# sensor.net
KiCad netlist of a schematic drawn in Altium Designer
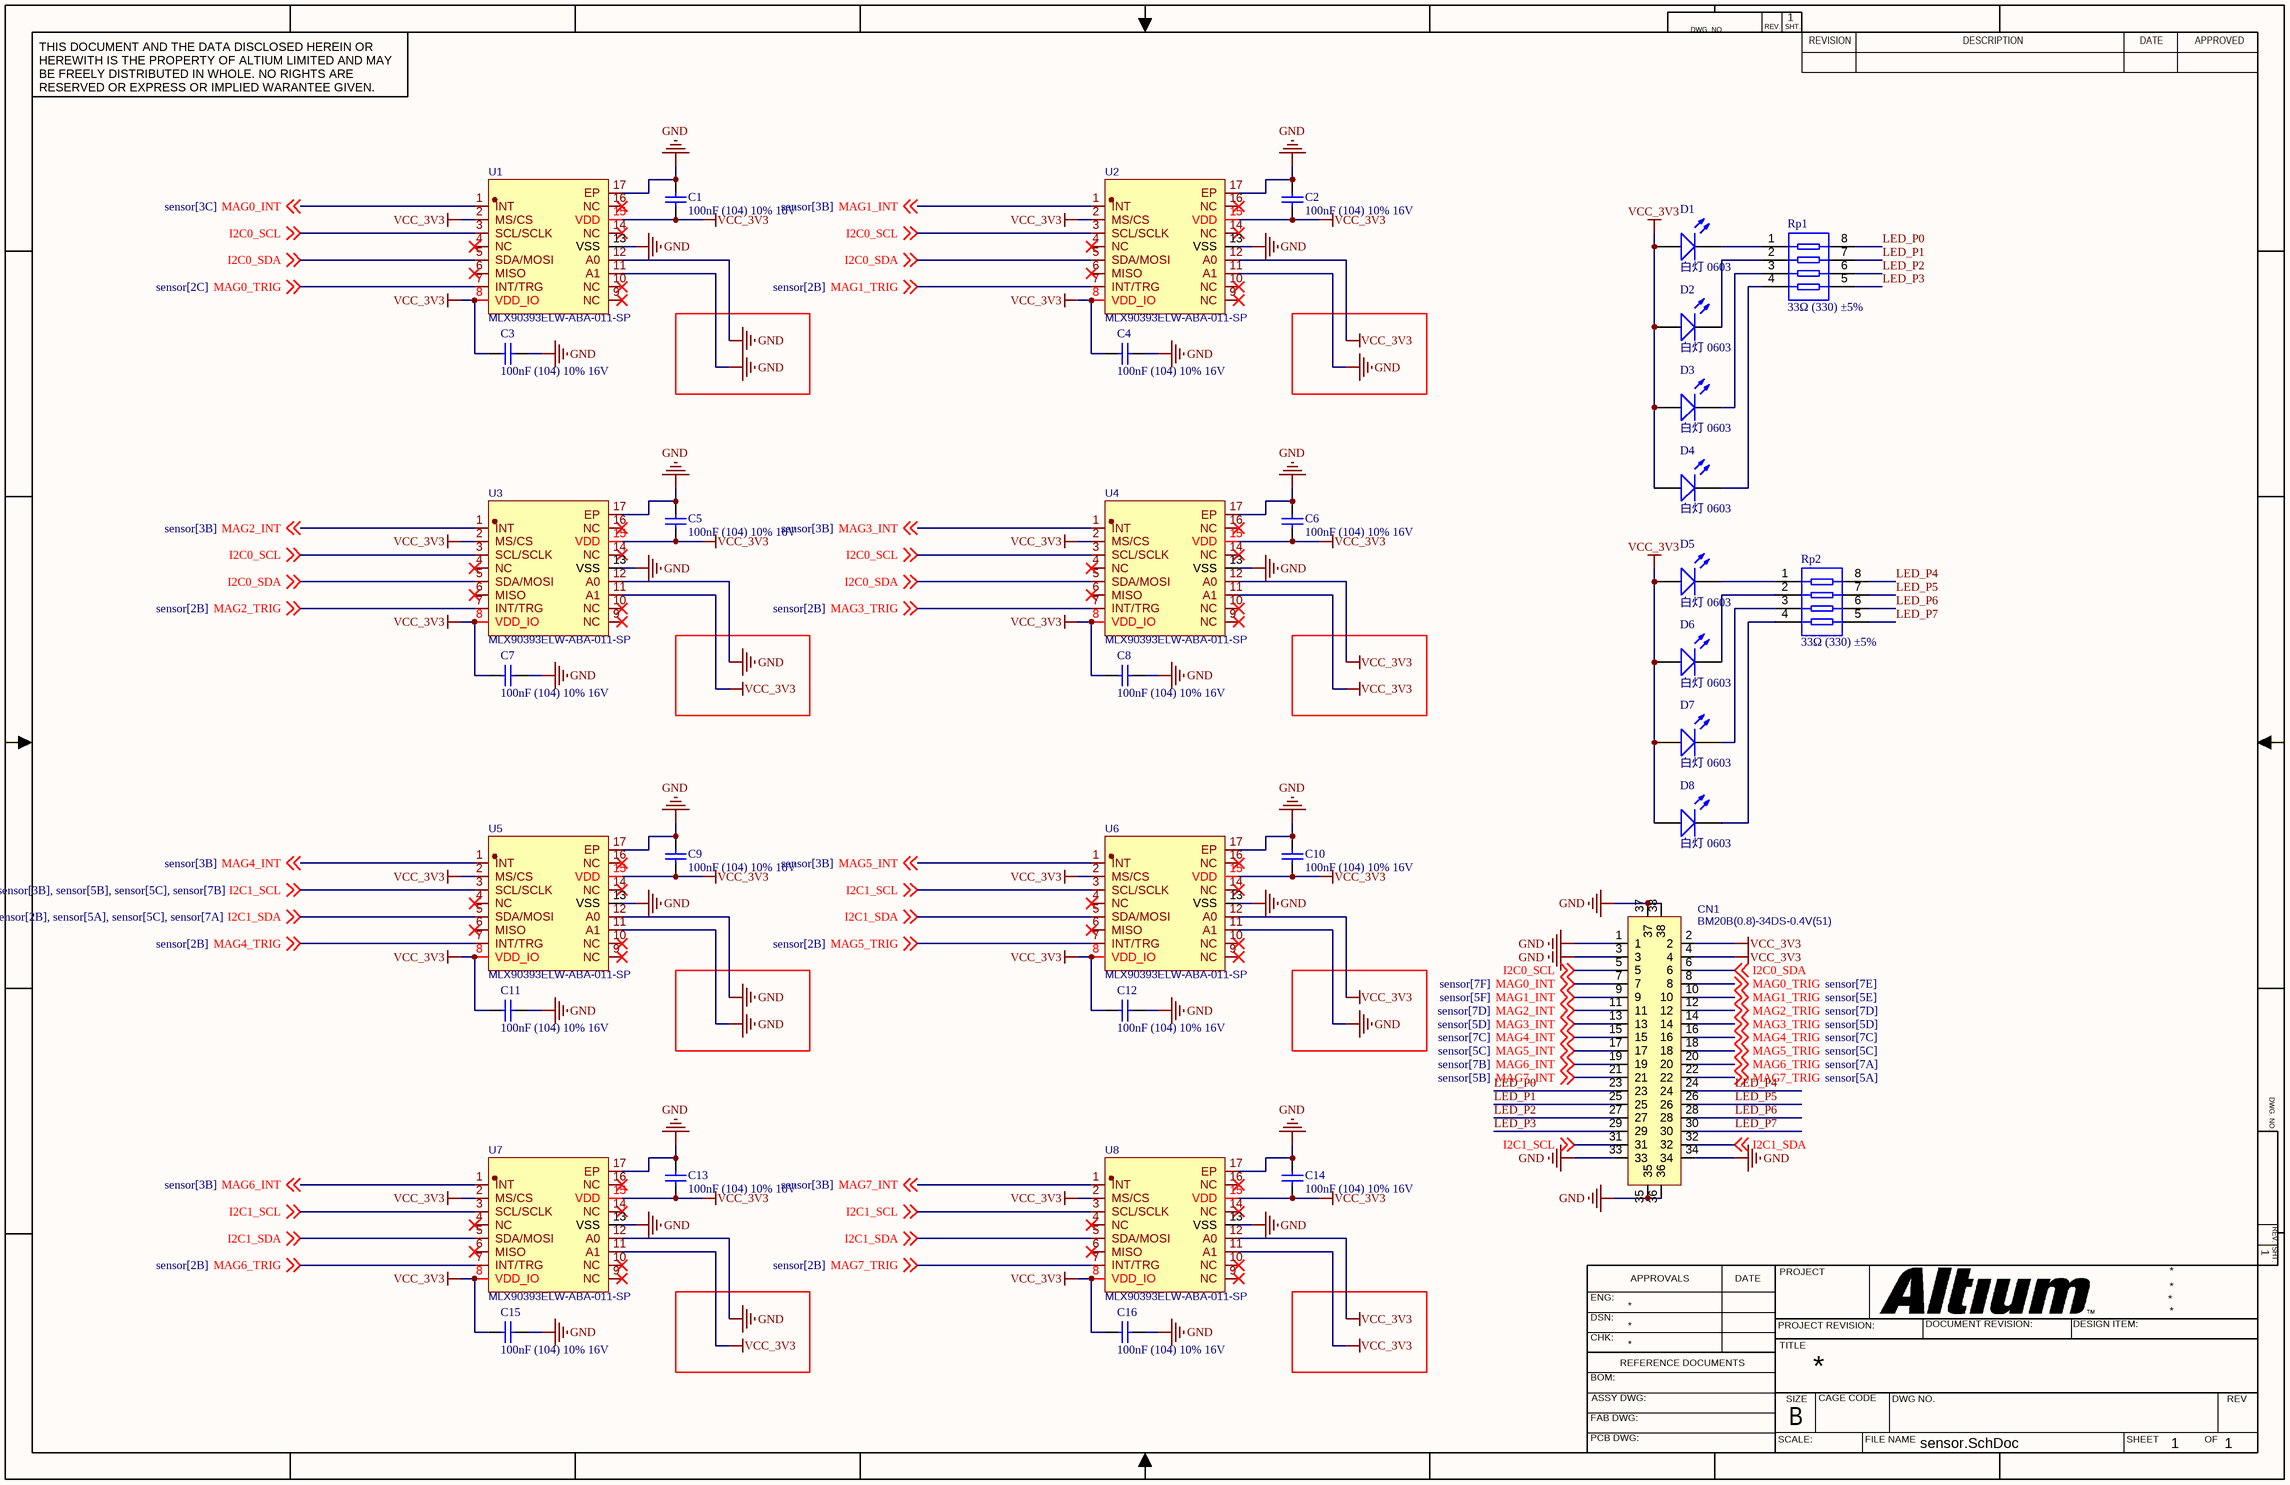
[diagram p0: sensor.SchDoc]

(export (version "E")
  (design (tool "Eeschema 10.0.6"))
  (components
    (comp (ref "C1")
      (value "100nF (104) 10% 16V")
      (footprint "LC-0402_C_NOSILK")
      (description "贴片电容")
      (libsource (lib "Miscellaneous Devices LC") (part "0402 100nF (104) 10% 16V"))
    )
    (comp (ref "C2")
      (value "100nF (104) 10% 16V")
      (footprint "LC-0402_C_NOSILK")
      (description "贴片电容")
      (libsource (lib "Miscellaneous Devices LC") (part "0402 100nF (104) 10% 16V"))
    )
    (comp (ref "C3")
      (value "100nF (104) 10% 16V")
      (footprint "LC-0402_C_NOSILK")
      (description "贴片电容")
      (libsource (lib "Miscellaneous Devices LC") (part "0402 100nF (104) 10% 16V"))
    )
    (comp (ref "C4")
      (value "100nF (104) 10% 16V")
      (footprint "LC-0402_C_NOSILK")
      (description "贴片电容")
      (libsource (lib "Miscellaneous Devices LC") (part "0402 100nF (104) 10% 16V"))
    )
    (comp (ref "C5")
      (value "100nF (104) 10% 16V")
      (footprint "LC-0402_C_NOSILK")
      (description "贴片电容")
      (libsource (lib "Miscellaneous Devices LC") (part "0402 100nF (104) 10% 16V"))
    )
    (comp (ref "C6")
      (value "100nF (104) 10% 16V")
      (footprint "LC-0402_C_NOSILK")
      (description "贴片电容")
      (libsource (lib "Miscellaneous Devices LC") (part "0402 100nF (104) 10% 16V"))
    )
    (comp (ref "C7")
      (value "100nF (104) 10% 16V")
      (footprint "LC-0402_C_NOSILK")
      (description "贴片电容")
      (libsource (lib "Miscellaneous Devices LC") (part "0402 100nF (104) 10% 16V"))
    )
    (comp (ref "C8")
      (value "100nF (104) 10% 16V")
      (footprint "LC-0402_C_NOSILK")
      (description "贴片电容")
      (libsource (lib "Miscellaneous Devices LC") (part "0402 100nF (104) 10% 16V"))
    )
    (comp (ref "C9")
      (value "100nF (104) 10% 16V")
      (footprint "LC-0402_C_NOSILK")
      (description "贴片电容")
      (libsource (lib "Miscellaneous Devices LC") (part "0402 100nF (104) 10% 16V"))
    )
    (comp (ref "C10")
      (value "100nF (104) 10% 16V")
      (footprint "LC-0402_C_NOSILK")
      (description "贴片电容")
      (libsource (lib "Miscellaneous Devices LC") (part "0402 100nF (104) 10% 16V"))
    )
    (comp (ref "C11")
      (value "100nF (104) 10% 16V")
      (footprint "LC-0402_C_NOSILK")
      (description "贴片电容")
      (libsource (lib "Miscellaneous Devices LC") (part "0402 100nF (104) 10% 16V"))
    )
    (comp (ref "C12")
      (value "100nF (104) 10% 16V")
      (footprint "LC-0402_C_NOSILK")
      (description "贴片电容")
      (libsource (lib "Miscellaneous Devices LC") (part "0402 100nF (104) 10% 16V"))
    )
    (comp (ref "C13")
      (value "100nF (104) 10% 16V")
      (footprint "LC-0402_C_NOSILK")
      (description "贴片电容")
      (libsource (lib "Miscellaneous Devices LC") (part "0402 100nF (104) 10% 16V"))
    )
    (comp (ref "C14")
      (value "100nF (104) 10% 16V")
      (footprint "LC-0402_C_NOSILK")
      (description "贴片电容")
      (libsource (lib "Miscellaneous Devices LC") (part "0402 100nF (104) 10% 16V"))
    )
    (comp (ref "C15")
      (value "100nF (104) 10% 16V")
      (footprint "LC-0402_C_NOSILK")
      (description "贴片电容")
      (libsource (lib "Miscellaneous Devices LC") (part "0402 100nF (104) 10% 16V"))
    )
    (comp (ref "C16")
      (value "100nF (104) 10% 16V")
      (footprint "LC-0402_C_NOSILK")
      (description "贴片电容")
      (libsource (lib "Miscellaneous Devices LC") (part "0402 100nF (104) 10% 16V"))
    )
    (comp (ref "CN1")
      (value "BM20B(0.8)-34DS-0.4V(51)")
      (footprint "CONN-SMD_34P-P0.40_BM20B-0.8-34DS-0.4V-51")
      (description "0.4mm BTB连接器-34P 母")
      (fields (field (name "BOM_SUPPLIER PART") "C424541") (field (name "CONTRIBUTOR") "LCSC"))
      (libsource (lib "merci") (part "BM20B(0.8)-34DS-0.4V(51)"))
    )
    (comp (ref "D1")
      (value "白灯 0603")
      (footprint "0603_LED_S1")
      (description "发光二极管")
      (libsource (lib "Miscellaneous Devices LC") (part "0603 白灯"))
    )
    (comp (ref "D2")
      (value "白灯 0603")
      (footprint "0603_LED_S1")
      (description "发光二极管")
      (libsource (lib "Miscellaneous Devices LC") (part "0603 白灯"))
    )
    (comp (ref "D3")
      (value "白灯 0603")
      (footprint "0603_LED_S1")
      (description "发光二极管")
      (libsource (lib "Miscellaneous Devices LC") (part "0603 白灯"))
    )
    (comp (ref "D4")
      (value "白灯 0603")
      (footprint "0603_LED_S1")
      (description "发光二极管")
      (libsource (lib "Miscellaneous Devices LC") (part "0603 白灯"))
    )
    (comp (ref "D5")
      (value "白灯 0603")
      (footprint "0603_LED_S1")
      (description "发光二极管")
      (libsource (lib "Miscellaneous Devices LC") (part "0603 白灯"))
    )
    (comp (ref "D6")
      (value "白灯 0603")
      (footprint "0603_LED_S1")
      (description "发光二极管")
      (libsource (lib "Miscellaneous Devices LC") (part "0603 白灯"))
    )
    (comp (ref "D7")
      (value "白灯 0603")
      (footprint "0603_LED_S1")
      (description "发光二极管")
      (libsource (lib "Miscellaneous Devices LC") (part "0603 白灯"))
    )
    (comp (ref "D8")
      (value "白灯 0603")
      (footprint "0603_LED_S1")
      (description "发光二极管")
      (libsource (lib "Miscellaneous Devices LC") (part "0603 白灯"))
    )
    (comp (ref "Rp1")
      (value "33Ω (330) ±5%")
      (footprint "0402_Rx4")
      (description "贴片排阻")
      (libsource (lib "Miscellaneous Devices LC") (part "0402*4 33Ω (330) 5%"))
    )
    (comp (ref "Rp2")
      (value "33Ω (330) ±5%")
      (footprint "0402_Rx4")
      (description "贴片排阻")
      (libsource (lib "Miscellaneous Devices LC") (part "0402*4 33Ω (330) 5%"))
    )
    (comp (ref "U1")
      (value "MLX90393ELW-ABA-011-SP")
      (footprint "QFN-16_L3.0-W3.0-P0.50-TR-EP1.7")
      (fields (field (name "BOM_SUPPLIER PART") "C1526586") (field (name "CONTRIBUTOR") "LCSC"))
      (libsource (lib "merci") (part "MLX90393ELW-ABA-011-SP"))
    )
    (comp (ref "U2")
      (value "MLX90393ELW-ABA-011-SP")
      (footprint "QFN-16_L3.0-W3.0-P0.50-TR-EP1.7")
      (fields (field (name "BOM_SUPPLIER PART") "C1526586") (field (name "CONTRIBUTOR") "LCSC"))
      (libsource (lib "merci") (part "MLX90393ELW-ABA-011-SP"))
    )
    (comp (ref "U3")
      (value "MLX90393ELW-ABA-011-SP")
      (footprint "QFN-16_L3.0-W3.0-P0.50-TR-EP1.7")
      (fields (field (name "BOM_SUPPLIER PART") "C1526586") (field (name "CONTRIBUTOR") "LCSC"))
      (libsource (lib "merci") (part "MLX90393ELW-ABA-011-SP"))
    )
    (comp (ref "U4")
      (value "MLX90393ELW-ABA-011-SP")
      (footprint "QFN-16_L3.0-W3.0-P0.50-TR-EP1.7")
      (fields (field (name "BOM_SUPPLIER PART") "C1526586") (field (name "CONTRIBUTOR") "LCSC"))
      (libsource (lib "merci") (part "MLX90393ELW-ABA-011-SP"))
    )
    (comp (ref "U5")
      (value "MLX90393ELW-ABA-011-SP")
      (footprint "QFN-16_L3.0-W3.0-P0.50-TR-EP1.7")
      (fields (field (name "BOM_SUPPLIER PART") "C1526586") (field (name "CONTRIBUTOR") "LCSC"))
      (libsource (lib "merci") (part "MLX90393ELW-ABA-011-SP"))
    )
    (comp (ref "U6")
      (value "MLX90393ELW-ABA-011-SP")
      (footprint "QFN-16_L3.0-W3.0-P0.50-TR-EP1.7")
      (fields (field (name "BOM_SUPPLIER PART") "C1526586") (field (name "CONTRIBUTOR") "LCSC"))
      (libsource (lib "merci") (part "MLX90393ELW-ABA-011-SP"))
    )
    (comp (ref "U7")
      (value "MLX90393ELW-ABA-011-SP")
      (footprint "QFN-16_L3.0-W3.0-P0.50-TR-EP1.7")
      (fields (field (name "BOM_SUPPLIER PART") "C1526586") (field (name "CONTRIBUTOR") "LCSC"))
      (libsource (lib "merci") (part "MLX90393ELW-ABA-011-SP"))
    )
    (comp (ref "U8")
      (value "MLX90393ELW-ABA-011-SP")
      (footprint "QFN-16_L3.0-W3.0-P0.50-TR-EP1.7")
      (fields (field (name "BOM_SUPPLIER PART") "C1526586") (field (name "CONTRIBUTOR") "LCSC"))
      (libsource (lib "merci") (part "MLX90393ELW-ABA-011-SP"))
    )
  )
  (nets
    (net (code "1") (name "/LED_P0") (class "Default")
      (node (ref "CN1") (pin "23") (pinfunction "23_23") (pintype "passive"))
      (node (ref "Rp1") (pin "8") (pinfunction "8_8") (pintype "passive"))
    )
    (net (code "2") (name "/LED_P1") (class "Default")
      (node (ref "CN1") (pin "25") (pinfunction "25_25") (pintype "passive"))
      (node (ref "Rp1") (pin "7") (pinfunction "7_7") (pintype "passive"))
    )
    (net (code "3") (name "/LED_P2") (class "Default")
      (node (ref "CN1") (pin "27") (pinfunction "27_27") (pintype "passive"))
      (node (ref "Rp1") (pin "6") (pinfunction "6_6") (pintype "passive"))
    )
    (net (code "4") (name "/LED_P3") (class "Default")
      (node (ref "CN1") (pin "29") (pinfunction "29_29") (pintype "passive"))
      (node (ref "Rp1") (pin "5") (pinfunction "5_5") (pintype "passive"))
    )
    (net (code "5") (name "/LED_P4") (class "Default")
      (node (ref "CN1") (pin "24") (pinfunction "24_24") (pintype "passive"))
      (node (ref "Rp2") (pin "8") (pinfunction "8_8") (pintype "passive"))
    )
    (net (code "6") (name "/LED_P5") (class "Default")
      (node (ref "CN1") (pin "26") (pinfunction "26_26") (pintype "passive"))
      (node (ref "Rp2") (pin "7") (pinfunction "7_7") (pintype "passive"))
    )
    (net (code "7") (name "/LED_P6") (class "Default")
      (node (ref "CN1") (pin "28") (pinfunction "28_28") (pintype "passive"))
      (node (ref "Rp2") (pin "6") (pinfunction "6_6") (pintype "passive"))
    )
    (net (code "8") (name "/LED_P7") (class "Default")
      (node (ref "CN1") (pin "30") (pinfunction "30_30") (pintype "passive"))
      (node (ref "Rp2") (pin "5") (pinfunction "5_5") (pintype "passive"))
    )
    (net (code "9") (name "GND") (class "Default")
      (node (ref "C1") (pin "2") (pinfunction "2_2") (pintype "passive"))
      (node (ref "C10") (pin "2") (pinfunction "2_2") (pintype "passive"))
      (node (ref "C11") (pin "2") (pinfunction "2_2") (pintype "passive"))
      (node (ref "C12") (pin "2") (pinfunction "2_2") (pintype "passive"))
      (node (ref "C13") (pin "2") (pinfunction "2_2") (pintype "passive"))
      (node (ref "C14") (pin "2") (pinfunction "2_2") (pintype "passive"))
      (node (ref "C15") (pin "2") (pinfunction "2_2") (pintype "passive"))
      (node (ref "C16") (pin "2") (pinfunction "2_2") (pintype "passive"))
      (node (ref "C2") (pin "2") (pinfunction "2_2") (pintype "passive"))
      (node (ref "C3") (pin "2") (pinfunction "2_2") (pintype "passive"))
      (node (ref "C4") (pin "2") (pinfunction "2_2") (pintype "passive"))
      (node (ref "C5") (pin "2") (pinfunction "2_2") (pintype "passive"))
      (node (ref "C6") (pin "2") (pinfunction "2_2") (pintype "passive"))
      (node (ref "C7") (pin "2") (pinfunction "2_2") (pintype "passive"))
      (node (ref "C8") (pin "2") (pinfunction "2_2") (pintype "passive"))
      (node (ref "C9") (pin "2") (pinfunction "2_2") (pintype "passive"))
      (node (ref "CN1") (pin "1") (pinfunction "1_1") (pintype "passive"))
      (node (ref "CN1") (pin "3") (pinfunction "3_3") (pintype "passive"))
      (node (ref "CN1") (pin "33") (pinfunction "33_33") (pintype "passive"))
      (node (ref "CN1") (pin "34") (pinfunction "34_34") (pintype "passive"))
      (node (ref "CN1") (pin "35") (pinfunction "35_35") (pintype "passive"))
      (node (ref "CN1") (pin "36") (pinfunction "36_36") (pintype "passive"))
      (node (ref "CN1") (pin "37") (pinfunction "37_37") (pintype "passive"))
      (node (ref "CN1") (pin "38") (pinfunction "38_38") (pintype "passive"))
      (node (ref "U1") (pin "11") (pinfunction "A1_11") (pintype "passive"))
      (node (ref "U1") (pin "12") (pinfunction "A0_12") (pintype "passive"))
      (node (ref "U1") (pin "13") (pinfunction "VSS_13") (pintype "passive"))
      (node (ref "U1") (pin "17") (pinfunction "EP_17") (pintype "passive"))
      (node (ref "U2") (pin "11") (pinfunction "A1_11") (pintype "passive"))
      (node (ref "U2") (pin "13") (pinfunction "VSS_13") (pintype "passive"))
      (node (ref "U2") (pin "17") (pinfunction "EP_17") (pintype "passive"))
      (node (ref "U3") (pin "12") (pinfunction "A0_12") (pintype "passive"))
      (node (ref "U3") (pin "13") (pinfunction "VSS_13") (pintype "passive"))
      (node (ref "U3") (pin "17") (pinfunction "EP_17") (pintype "passive"))
      (node (ref "U4") (pin "13") (pinfunction "VSS_13") (pintype "passive"))
      (node (ref "U4") (pin "17") (pinfunction "EP_17") (pintype "passive"))
      (node (ref "U5") (pin "11") (pinfunction "A1_11") (pintype "passive"))
      (node (ref "U5") (pin "12") (pinfunction "A0_12") (pintype "passive"))
      (node (ref "U5") (pin "13") (pinfunction "VSS_13") (pintype "passive"))
      (node (ref "U5") (pin "17") (pinfunction "EP_17") (pintype "passive"))
      (node (ref "U6") (pin "11") (pinfunction "A1_11") (pintype "passive"))
      (node (ref "U6") (pin "13") (pinfunction "VSS_13") (pintype "passive"))
      (node (ref "U6") (pin "17") (pinfunction "EP_17") (pintype "passive"))
      (node (ref "U7") (pin "12") (pinfunction "A0_12") (pintype "passive"))
      (node (ref "U7") (pin "13") (pinfunction "VSS_13") (pintype "passive"))
      (node (ref "U7") (pin "17") (pinfunction "EP_17") (pintype "passive"))
      (node (ref "U8") (pin "13") (pinfunction "VSS_13") (pintype "passive"))
      (node (ref "U8") (pin "17") (pinfunction "EP_17") (pintype "passive"))
    )
    (net (code "10") (name "I2C0_SCL") (class "Default")
      (node (ref "CN1") (pin "5") (pinfunction "5_5") (pintype "passive"))
      (node (ref "U1") (pin "3") (pinfunction "SCL/SCLK_3") (pintype "passive"))
      (node (ref "U2") (pin "3") (pinfunction "SCL/SCLK_3") (pintype "passive"))
      (node (ref "U3") (pin "3") (pinfunction "SCL/SCLK_3") (pintype "passive"))
      (node (ref "U4") (pin "3") (pinfunction "SCL/SCLK_3") (pintype "passive"))
    )
    (net (code "11") (name "I2C0_SDA") (class "Default")
      (node (ref "CN1") (pin "6") (pinfunction "6_6") (pintype "passive"))
      (node (ref "U1") (pin "5") (pinfunction "SDA/MOSI_5") (pintype "passive"))
      (node (ref "U2") (pin "5") (pinfunction "SDA/MOSI_5") (pintype "passive"))
      (node (ref "U3") (pin "5") (pinfunction "SDA/MOSI_5") (pintype "passive"))
      (node (ref "U4") (pin "5") (pinfunction "SDA/MOSI_5") (pintype "passive"))
    )
    (net (code "12") (name "I2C1_SCL") (class "Default")
      (node (ref "CN1") (pin "31") (pinfunction "31_31") (pintype "passive"))
      (node (ref "U5") (pin "3") (pinfunction "SCL/SCLK_3") (pintype "passive"))
      (node (ref "U6") (pin "3") (pinfunction "SCL/SCLK_3") (pintype "passive"))
      (node (ref "U7") (pin "3") (pinfunction "SCL/SCLK_3") (pintype "passive"))
      (node (ref "U8") (pin "3") (pinfunction "SCL/SCLK_3") (pintype "passive"))
    )
    (net (code "13") (name "I2C1_SDA") (class "Default")
      (node (ref "CN1") (pin "32") (pinfunction "32_32") (pintype "passive"))
      (node (ref "U5") (pin "5") (pinfunction "SDA/MOSI_5") (pintype "passive"))
      (node (ref "U6") (pin "5") (pinfunction "SDA/MOSI_5") (pintype "passive"))
      (node (ref "U7") (pin "5") (pinfunction "SDA/MOSI_5") (pintype "passive"))
      (node (ref "U8") (pin "5") (pinfunction "SDA/MOSI_5") (pintype "passive"))
    )
    (net (code "14") (name "MAG0_INT") (class "Default")
      (node (ref "CN1") (pin "7") (pinfunction "7_7") (pintype "passive"))
      (node (ref "U1") (pin "1") (pinfunction "INT_1") (pintype "passive"))
    )
    (net (code "15") (name "MAG0_TRIG") (class "Default")
      (node (ref "CN1") (pin "8") (pinfunction "8_8") (pintype "passive"))
      (node (ref "U1") (pin "7") (pinfunction "INT/TRG_7") (pintype "passive"))
    )
    (net (code "16") (name "MAG1_INT") (class "Default")
      (node (ref "CN1") (pin "9") (pinfunction "9_9") (pintype "passive"))
      (node (ref "U2") (pin "1") (pinfunction "INT_1") (pintype "passive"))
    )
    (net (code "17") (name "MAG1_TRIG") (class "Default")
      (node (ref "CN1") (pin "10") (pinfunction "10_10") (pintype "passive"))
      (node (ref "U2") (pin "7") (pinfunction "INT/TRG_7") (pintype "passive"))
    )
    (net (code "18") (name "MAG2_INT") (class "Default")
      (node (ref "CN1") (pin "11") (pinfunction "11_11") (pintype "passive"))
      (node (ref "U3") (pin "1") (pinfunction "INT_1") (pintype "passive"))
    )
    (net (code "19") (name "MAG2_TRIG") (class "Default")
      (node (ref "CN1") (pin "12") (pinfunction "12_12") (pintype "passive"))
      (node (ref "U3") (pin "7") (pinfunction "INT/TRG_7") (pintype "passive"))
    )
    (net (code "20") (name "MAG3_INT") (class "Default")
      (node (ref "CN1") (pin "13") (pinfunction "13_13") (pintype "passive"))
      (node (ref "U4") (pin "1") (pinfunction "INT_1") (pintype "passive"))
    )
    (net (code "21") (name "MAG3_TRIG") (class "Default")
      (node (ref "CN1") (pin "14") (pinfunction "14_14") (pintype "passive"))
      (node (ref "U4") (pin "7") (pinfunction "INT/TRG_7") (pintype "passive"))
    )
    (net (code "22") (name "MAG4_INT") (class "Default")
      (node (ref "CN1") (pin "15") (pinfunction "15_15") (pintype "passive"))
      (node (ref "U5") (pin "1") (pinfunction "INT_1") (pintype "passive"))
    )
    (net (code "23") (name "MAG4_TRIG") (class "Default")
      (node (ref "CN1") (pin "16") (pinfunction "16_16") (pintype "passive"))
      (node (ref "U5") (pin "7") (pinfunction "INT/TRG_7") (pintype "passive"))
    )
    (net (code "24") (name "MAG5_INT") (class "Default")
      (node (ref "CN1") (pin "17") (pinfunction "17_17") (pintype "passive"))
      (node (ref "U6") (pin "1") (pinfunction "INT_1") (pintype "passive"))
    )
    (net (code "25") (name "MAG5_TRIG") (class "Default")
      (node (ref "CN1") (pin "18") (pinfunction "18_18") (pintype "passive"))
      (node (ref "U6") (pin "7") (pinfunction "INT/TRG_7") (pintype "passive"))
    )
    (net (code "26") (name "MAG6_INT") (class "Default")
      (node (ref "CN1") (pin "19") (pinfunction "19_19") (pintype "passive"))
      (node (ref "U7") (pin "1") (pinfunction "INT_1") (pintype "passive"))
    )
    (net (code "27") (name "MAG6_TRIG") (class "Default")
      (node (ref "CN1") (pin "20") (pinfunction "20_20") (pintype "passive"))
      (node (ref "U7") (pin "7") (pinfunction "INT/TRG_7") (pintype "passive"))
    )
    (net (code "28") (name "MAG7_INT") (class "Default")
      (node (ref "CN1") (pin "21") (pinfunction "21_21") (pintype "passive"))
      (node (ref "U8") (pin "1") (pinfunction "INT_1") (pintype "passive"))
    )
    (net (code "29") (name "MAG7_TRIG") (class "Default")
      (node (ref "CN1") (pin "22") (pinfunction "22_22") (pintype "passive"))
      (node (ref "U8") (pin "7") (pinfunction "INT/TRG_7") (pintype "passive"))
    )
    (net (code "30") (name "Net-(D1-PadK)") (class "Default")
      (node (ref "D1") (pin "K") (pinfunction "K_K") (pintype "passive"))
      (node (ref "Rp1") (pin "1") (pinfunction "1_1") (pintype "passive"))
    )
    (net (code "31") (name "Net-(D2-PadK)") (class "Default")
      (node (ref "D2") (pin "K") (pinfunction "K_K") (pintype "passive"))
      (node (ref "Rp1") (pin "2") (pinfunction "2_2") (pintype "passive"))
    )
    (net (code "32") (name "Net-(D3-PadK)") (class "Default")
      (node (ref "D3") (pin "K") (pinfunction "K_K") (pintype "passive"))
      (node (ref "Rp1") (pin "3") (pinfunction "3_3") (pintype "passive"))
    )
    (net (code "33") (name "Net-(D4-PadK)") (class "Default")
      (node (ref "D4") (pin "K") (pinfunction "K_K") (pintype "passive"))
      (node (ref "Rp1") (pin "4") (pinfunction "4_4") (pintype "passive"))
    )
    (net (code "34") (name "Net-(D5-PadK)") (class "Default")
      (node (ref "D5") (pin "K") (pinfunction "K_K") (pintype "passive"))
      (node (ref "Rp2") (pin "1") (pinfunction "1_1") (pintype "passive"))
    )
    (net (code "35") (name "Net-(D6-PadK)") (class "Default")
      (node (ref "D6") (pin "K") (pinfunction "K_K") (pintype "passive"))
      (node (ref "Rp2") (pin "2") (pinfunction "2_2") (pintype "passive"))
    )
    (net (code "36") (name "Net-(D7-PadK)") (class "Default")
      (node (ref "D7") (pin "K") (pinfunction "K_K") (pintype "passive"))
      (node (ref "Rp2") (pin "3") (pinfunction "3_3") (pintype "passive"))
    )
    (net (code "37") (name "Net-(D8-PadK)") (class "Default")
      (node (ref "D8") (pin "K") (pinfunction "K_K") (pintype "passive"))
      (node (ref "Rp2") (pin "4") (pinfunction "4_4") (pintype "passive"))
    )
    (net (code "38") (name "VCC_3V3") (class "Default")
      (node (ref "C1") (pin "1") (pinfunction "1_1") (pintype "passive"))
      (node (ref "C10") (pin "1") (pinfunction "1_1") (pintype "passive"))
      (node (ref "C11") (pin "1") (pinfunction "1_1") (pintype "passive"))
      (node (ref "C12") (pin "1") (pinfunction "1_1") (pintype "passive"))
      (node (ref "C13") (pin "1") (pinfunction "1_1") (pintype "passive"))
      (node (ref "C14") (pin "1") (pinfunction "1_1") (pintype "passive"))
      (node (ref "C15") (pin "1") (pinfunction "1_1") (pintype "passive"))
      (node (ref "C16") (pin "1") (pinfunction "1_1") (pintype "passive"))
      (node (ref "C2") (pin "1") (pinfunction "1_1") (pintype "passive"))
      (node (ref "C3") (pin "1") (pinfunction "1_1") (pintype "passive"))
      (node (ref "C4") (pin "1") (pinfunction "1_1") (pintype "passive"))
      (node (ref "C5") (pin "1") (pinfunction "1_1") (pintype "passive"))
      (node (ref "C6") (pin "1") (pinfunction "1_1") (pintype "passive"))
      (node (ref "C7") (pin "1") (pinfunction "1_1") (pintype "passive"))
      (node (ref "C8") (pin "1") (pinfunction "1_1") (pintype "passive"))
      (node (ref "C9") (pin "1") (pinfunction "1_1") (pintype "passive"))
      (node (ref "CN1") (pin "2") (pinfunction "2_2") (pintype "passive"))
      (node (ref "CN1") (pin "4") (pinfunction "4_4") (pintype "passive"))
      (node (ref "D1") (pin "A") (pinfunction "A_A") (pintype "passive"))
      (node (ref "D2") (pin "A") (pinfunction "A_A") (pintype "passive"))
      (node (ref "D3") (pin "A") (pinfunction "A_A") (pintype "passive"))
      (node (ref "D4") (pin "A") (pinfunction "A_A") (pintype "passive"))
      (node (ref "D5") (pin "A") (pinfunction "A_A") (pintype "passive"))
      (node (ref "D6") (pin "A") (pinfunction "A_A") (pintype "passive"))
      (node (ref "D7") (pin "A") (pinfunction "A_A") (pintype "passive"))
      (node (ref "D8") (pin "A") (pinfunction "A_A") (pintype "passive"))
      (node (ref "U1") (pin "15") (pinfunction "VDD_15") (pintype "passive"))
      (node (ref "U1") (pin "2") (pinfunction "MS/CS_2") (pintype "passive"))
      (node (ref "U1") (pin "8") (pinfunction "VDD_IO_8") (pintype "passive"))
      (node (ref "U2") (pin "12") (pinfunction "A0_12") (pintype "passive"))
      (node (ref "U2") (pin "15") (pinfunction "VDD_15") (pintype "passive"))
      (node (ref "U2") (pin "2") (pinfunction "MS/CS_2") (pintype "passive"))
      (node (ref "U2") (pin "8") (pinfunction "VDD_IO_8") (pintype "passive"))
      (node (ref "U3") (pin "11") (pinfunction "A1_11") (pintype "passive"))
      (node (ref "U3") (pin "15") (pinfunction "VDD_15") (pintype "passive"))
      (node (ref "U3") (pin "2") (pinfunction "MS/CS_2") (pintype "passive"))
      (node (ref "U3") (pin "8") (pinfunction "VDD_IO_8") (pintype "passive"))
      (node (ref "U4") (pin "11") (pinfunction "A1_11") (pintype "passive"))
      (node (ref "U4") (pin "12") (pinfunction "A0_12") (pintype "passive"))
      (node (ref "U4") (pin "15") (pinfunction "VDD_15") (pintype "passive"))
      (node (ref "U4") (pin "2") (pinfunction "MS/CS_2") (pintype "passive"))
      (node (ref "U4") (pin "8") (pinfunction "VDD_IO_8") (pintype "passive"))
      (node (ref "U5") (pin "15") (pinfunction "VDD_15") (pintype "passive"))
      (node (ref "U5") (pin "2") (pinfunction "MS/CS_2") (pintype "passive"))
      (node (ref "U5") (pin "8") (pinfunction "VDD_IO_8") (pintype "passive"))
      (node (ref "U6") (pin "12") (pinfunction "A0_12") (pintype "passive"))
      (node (ref "U6") (pin "15") (pinfunction "VDD_15") (pintype "passive"))
      (node (ref "U6") (pin "2") (pinfunction "MS/CS_2") (pintype "passive"))
      (node (ref "U6") (pin "8") (pinfunction "VDD_IO_8") (pintype "passive"))
      (node (ref "U7") (pin "11") (pinfunction "A1_11") (pintype "passive"))
      (node (ref "U7") (pin "15") (pinfunction "VDD_15") (pintype "passive"))
      (node (ref "U7") (pin "2") (pinfunction "MS/CS_2") (pintype "passive"))
      (node (ref "U7") (pin "8") (pinfunction "VDD_IO_8") (pintype "passive"))
      (node (ref "U8") (pin "11") (pinfunction "A1_11") (pintype "passive"))
      (node (ref "U8") (pin "12") (pinfunction "A0_12") (pintype "passive"))
      (node (ref "U8") (pin "15") (pinfunction "VDD_15") (pintype "passive"))
      (node (ref "U8") (pin "2") (pinfunction "MS/CS_2") (pintype "passive"))
      (node (ref "U8") (pin "8") (pinfunction "VDD_IO_8") (pintype "passive"))
    )
    (net (code "39") (name "unconnected-(U1-MISO-Pad6)") (class "Default")
      (node (ref "U1") (pin "6") (pinfunction "MISO_6") (pintype "passive+no_connect"))
    )
    (net (code "40") (name "unconnected-(U1-NC-Pad4)") (class "Default")
      (node (ref "U1") (pin "4") (pinfunction "NC_4") (pintype "passive+no_connect"))
    )
    (net (code "41") (name "unconnected-(U1-NC-Pad9)") (class "Default")
      (node (ref "U1") (pin "9") (pinfunction "NC_9") (pintype "passive+no_connect"))
    )
    (net (code "42") (name "unconnected-(U1-NC-Pad10)") (class "Default")
      (node (ref "U1") (pin "10") (pinfunction "NC_10") (pintype "passive+no_connect"))
    )
    (net (code "43") (name "unconnected-(U1-NC-Pad14)") (class "Default")
      (node (ref "U1") (pin "14") (pinfunction "NC_14") (pintype "passive+no_connect"))
    )
    (net (code "44") (name "unconnected-(U1-NC-Pad16)") (class "Default")
      (node (ref "U1") (pin "16") (pinfunction "NC_16") (pintype "passive+no_connect"))
    )
    (net (code "45") (name "unconnected-(U2-MISO-Pad6)") (class "Default")
      (node (ref "U2") (pin "6") (pinfunction "MISO_6") (pintype "passive+no_connect"))
    )
    (net (code "46") (name "unconnected-(U2-NC-Pad4)") (class "Default")
      (node (ref "U2") (pin "4") (pinfunction "NC_4") (pintype "passive+no_connect"))
    )
    (net (code "47") (name "unconnected-(U2-NC-Pad9)") (class "Default")
      (node (ref "U2") (pin "9") (pinfunction "NC_9") (pintype "passive+no_connect"))
    )
    (net (code "48") (name "unconnected-(U2-NC-Pad10)") (class "Default")
      (node (ref "U2") (pin "10") (pinfunction "NC_10") (pintype "passive+no_connect"))
    )
    (net (code "49") (name "unconnected-(U2-NC-Pad14)") (class "Default")
      (node (ref "U2") (pin "14") (pinfunction "NC_14") (pintype "passive+no_connect"))
    )
    (net (code "50") (name "unconnected-(U2-NC-Pad16)") (class "Default")
      (node (ref "U2") (pin "16") (pinfunction "NC_16") (pintype "passive+no_connect"))
    )
    (net (code "51") (name "unconnected-(U3-MISO-Pad6)") (class "Default")
      (node (ref "U3") (pin "6") (pinfunction "MISO_6") (pintype "passive+no_connect"))
    )
    (net (code "52") (name "unconnected-(U3-NC-Pad4)") (class "Default")
      (node (ref "U3") (pin "4") (pinfunction "NC_4") (pintype "passive+no_connect"))
    )
    (net (code "53") (name "unconnected-(U3-NC-Pad9)") (class "Default")
      (node (ref "U3") (pin "9") (pinfunction "NC_9") (pintype "passive+no_connect"))
    )
    (net (code "54") (name "unconnected-(U3-NC-Pad10)") (class "Default")
      (node (ref "U3") (pin "10") (pinfunction "NC_10") (pintype "passive+no_connect"))
    )
    (net (code "55") (name "unconnected-(U3-NC-Pad14)") (class "Default")
      (node (ref "U3") (pin "14") (pinfunction "NC_14") (pintype "passive+no_connect"))
    )
    (net (code "56") (name "unconnected-(U3-NC-Pad16)") (class "Default")
      (node (ref "U3") (pin "16") (pinfunction "NC_16") (pintype "passive+no_connect"))
    )
    (net (code "57") (name "unconnected-(U4-MISO-Pad6)") (class "Default")
      (node (ref "U4") (pin "6") (pinfunction "MISO_6") (pintype "passive+no_connect"))
    )
    (net (code "58") (name "unconnected-(U4-NC-Pad4)") (class "Default")
      (node (ref "U4") (pin "4") (pinfunction "NC_4") (pintype "passive+no_connect"))
    )
    (net (code "59") (name "unconnected-(U4-NC-Pad9)") (class "Default")
      (node (ref "U4") (pin "9") (pinfunction "NC_9") (pintype "passive+no_connect"))
    )
    (net (code "60") (name "unconnected-(U4-NC-Pad10)") (class "Default")
      (node (ref "U4") (pin "10") (pinfunction "NC_10") (pintype "passive+no_connect"))
    )
    (net (code "61") (name "unconnected-(U4-NC-Pad14)") (class "Default")
      (node (ref "U4") (pin "14") (pinfunction "NC_14") (pintype "passive+no_connect"))
    )
    (net (code "62") (name "unconnected-(U4-NC-Pad16)") (class "Default")
      (node (ref "U4") (pin "16") (pinfunction "NC_16") (pintype "passive+no_connect"))
    )
    (net (code "63") (name "unconnected-(U5-MISO-Pad6)") (class "Default")
      (node (ref "U5") (pin "6") (pinfunction "MISO_6") (pintype "passive+no_connect"))
    )
    (net (code "64") (name "unconnected-(U5-NC-Pad4)") (class "Default")
      (node (ref "U5") (pin "4") (pinfunction "NC_4") (pintype "passive+no_connect"))
    )
    (net (code "65") (name "unconnected-(U5-NC-Pad9)") (class "Default")
      (node (ref "U5") (pin "9") (pinfunction "NC_9") (pintype "passive+no_connect"))
    )
    (net (code "66") (name "unconnected-(U5-NC-Pad10)") (class "Default")
      (node (ref "U5") (pin "10") (pinfunction "NC_10") (pintype "passive+no_connect"))
    )
    (net (code "67") (name "unconnected-(U5-NC-Pad14)") (class "Default")
      (node (ref "U5") (pin "14") (pinfunction "NC_14") (pintype "passive+no_connect"))
    )
    (net (code "68") (name "unconnected-(U5-NC-Pad16)") (class "Default")
      (node (ref "U5") (pin "16") (pinfunction "NC_16") (pintype "passive+no_connect"))
    )
    (net (code "69") (name "unconnected-(U6-MISO-Pad6)") (class "Default")
      (node (ref "U6") (pin "6") (pinfunction "MISO_6") (pintype "passive+no_connect"))
    )
    (net (code "70") (name "unconnected-(U6-NC-Pad4)") (class "Default")
      (node (ref "U6") (pin "4") (pinfunction "NC_4") (pintype "passive+no_connect"))
    )
    (net (code "71") (name "unconnected-(U6-NC-Pad9)") (class "Default")
      (node (ref "U6") (pin "9") (pinfunction "NC_9") (pintype "passive+no_connect"))
    )
    (net (code "72") (name "unconnected-(U6-NC-Pad10)") (class "Default")
      (node (ref "U6") (pin "10") (pinfunction "NC_10") (pintype "passive+no_connect"))
    )
    (net (code "73") (name "unconnected-(U6-NC-Pad14)") (class "Default")
      (node (ref "U6") (pin "14") (pinfunction "NC_14") (pintype "passive+no_connect"))
    )
    (net (code "74") (name "unconnected-(U6-NC-Pad16)") (class "Default")
      (node (ref "U6") (pin "16") (pinfunction "NC_16") (pintype "passive+no_connect"))
    )
    (net (code "75") (name "unconnected-(U7-MISO-Pad6)") (class "Default")
      (node (ref "U7") (pin "6") (pinfunction "MISO_6") (pintype "passive+no_connect"))
    )
    (net (code "76") (name "unconnected-(U7-NC-Pad4)") (class "Default")
      (node (ref "U7") (pin "4") (pinfunction "NC_4") (pintype "passive+no_connect"))
    )
    (net (code "77") (name "unconnected-(U7-NC-Pad9)") (class "Default")
      (node (ref "U7") (pin "9") (pinfunction "NC_9") (pintype "passive+no_connect"))
    )
    (net (code "78") (name "unconnected-(U7-NC-Pad10)") (class "Default")
      (node (ref "U7") (pin "10") (pinfunction "NC_10") (pintype "passive+no_connect"))
    )
    (net (code "79") (name "unconnected-(U7-NC-Pad14)") (class "Default")
      (node (ref "U7") (pin "14") (pinfunction "NC_14") (pintype "passive+no_connect"))
    )
    (net (code "80") (name "unconnected-(U7-NC-Pad16)") (class "Default")
      (node (ref "U7") (pin "16") (pinfunction "NC_16") (pintype "passive+no_connect"))
    )
    (net (code "81") (name "unconnected-(U8-MISO-Pad6)") (class "Default")
      (node (ref "U8") (pin "6") (pinfunction "MISO_6") (pintype "passive+no_connect"))
    )
    (net (code "82") (name "unconnected-(U8-NC-Pad4)") (class "Default")
      (node (ref "U8") (pin "4") (pinfunction "NC_4") (pintype "passive+no_connect"))
    )
    (net (code "83") (name "unconnected-(U8-NC-Pad9)") (class "Default")
      (node (ref "U8") (pin "9") (pinfunction "NC_9") (pintype "passive+no_connect"))
    )
    (net (code "84") (name "unconnected-(U8-NC-Pad10)") (class "Default")
      (node (ref "U8") (pin "10") (pinfunction "NC_10") (pintype "passive+no_connect"))
    )
    (net (code "85") (name "unconnected-(U8-NC-Pad14)") (class "Default")
      (node (ref "U8") (pin "14") (pinfunction "NC_14") (pintype "passive+no_connect"))
    )
    (net (code "86") (name "unconnected-(U8-NC-Pad16)") (class "Default")
      (node (ref "U8") (pin "16") (pinfunction "NC_16") (pintype "passive+no_connect"))
    )
  )
)
